# ATMEGA328.net
KiCad netlist of a schematic drawn in EAGLE
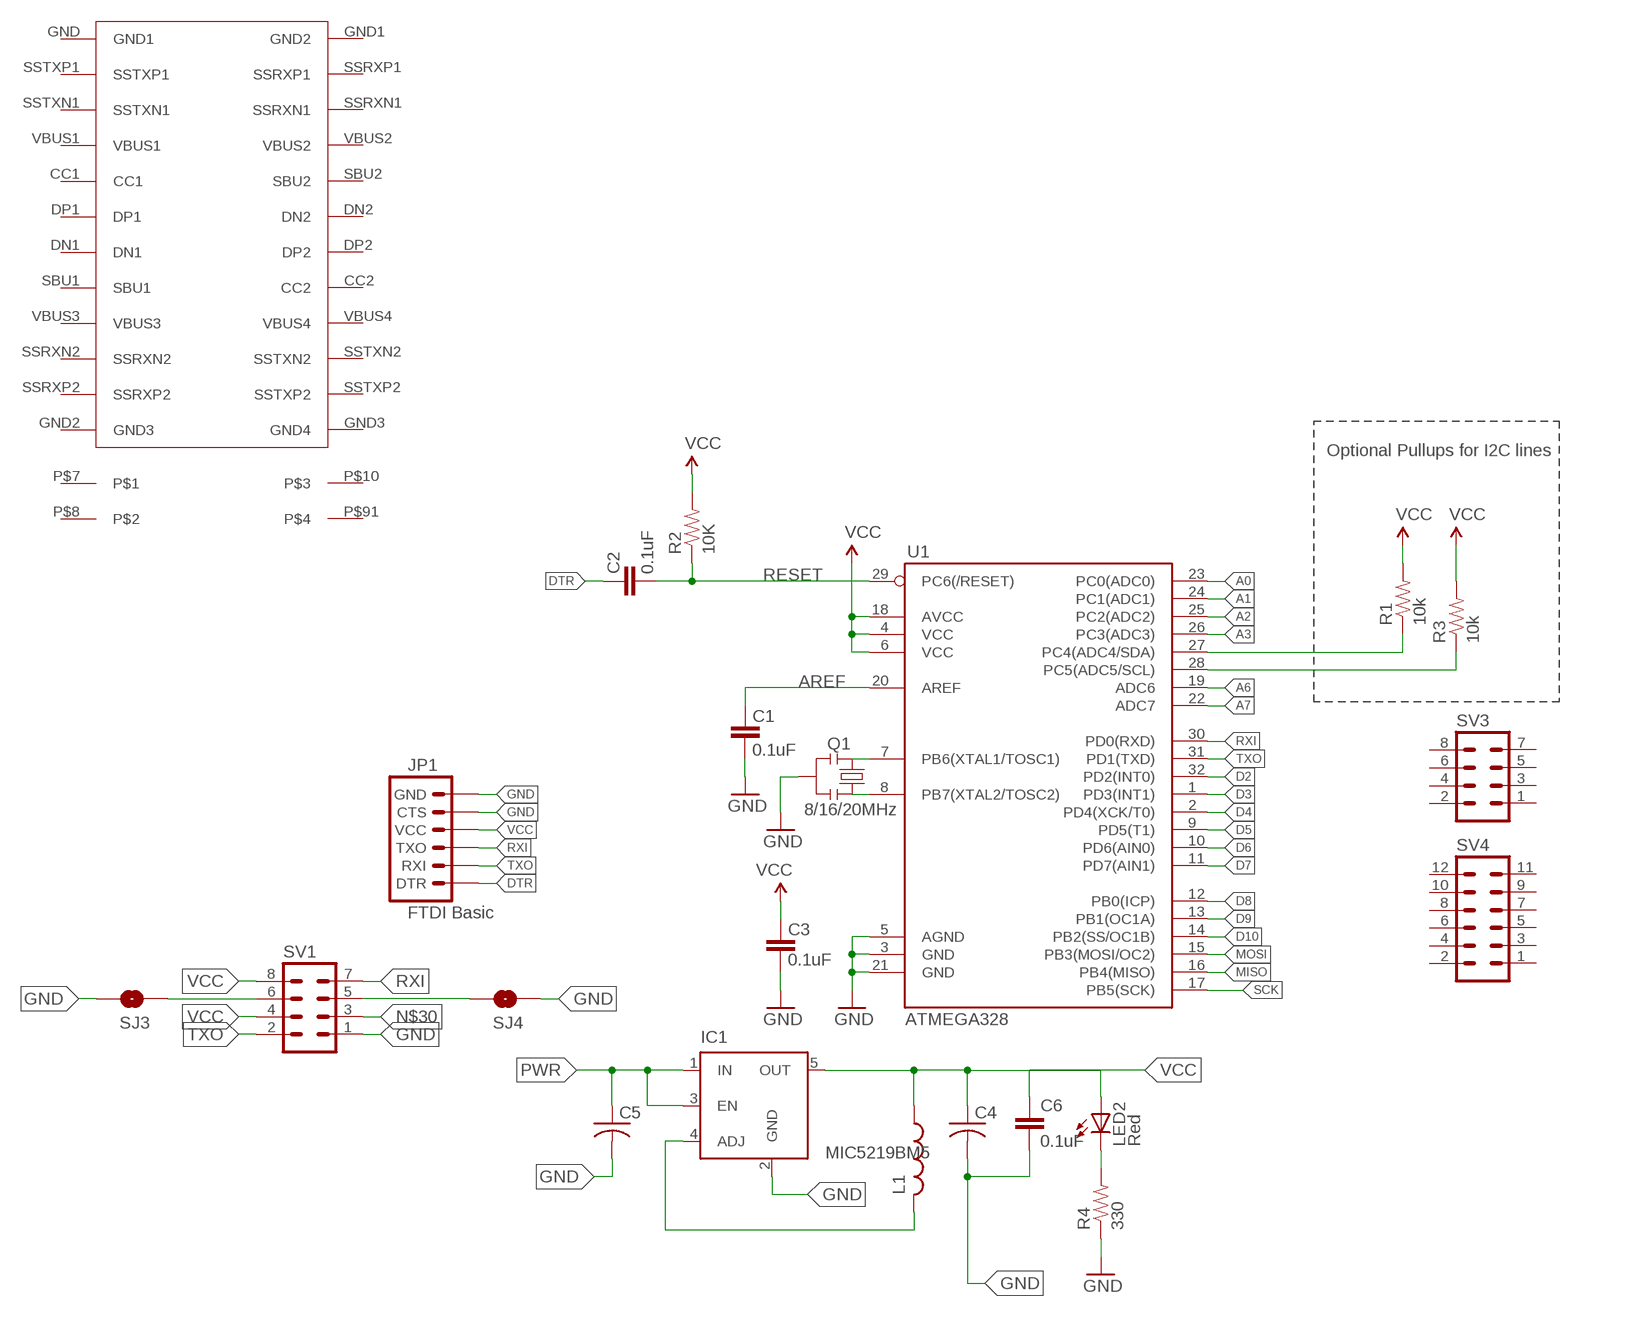
[diagram p0: schematic, sheet 1]

(export (version "E")
  (design (tool "Eeschema 10.0.6"))
  (components
    (comp (ref "C1")
      (value "0.1uF")
      (footprint "eagle-import:0603-CAP")
      (libsource (lib "eagle-import") (part "CAP0603-CAP"))
    )
    (comp (ref "C2")
      (value "0.1uF")
      (footprint "eagle-import:0603-CAP")
      (libsource (lib "eagle-import") (part "CAP0603-CAP"))
    )
    (comp (ref "C3")
      (value "0.1uF")
      (footprint "eagle-import:0603-CAP")
      (libsource (lib "eagle-import") (part "CAP0603-CAP"))
    )
    (comp (ref "C4")
      (value "C-USC0805K")
      (footprint "eagle-import:C0805K")
      (libsource (lib "eagle-import") (part "C-USC0805K"))
    )
    (comp (ref "C5")
      (value "C-USC0805K")
      (footprint "eagle-import:C0805K")
      (libsource (lib "eagle-import") (part "C-USC0805K"))
    )
    (comp (ref "C6")
      (value "0.1uF")
      (footprint "eagle-import:0603-CAP")
      (libsource (lib "eagle-import") (part "CAP0603-CAP"))
    )
    (comp (ref "IC1")
      (value "MIC5219BM5")
      (footprint "eagle-import:SOT23-5")
      (fields (field (name "MF") "ALTERA CORPORATION") (field (name "MPN") "MIC5219BM5 TR"))
      (libsource (lib "eagle-import") (part "MIC5219BM5"))
    )
    (comp (ref "JP1")
      (value "FTDI Basic")
      (footprint "eagle-import:1X06")
      (libsource (lib "eagle-import") (part "ARDUINO_SERIAL_PROGRAMPTH"))
    )
    (comp (ref "L1")
      (value "L-USL2012C")
      (footprint "eagle-import:L2012C")
      (libsource (lib "eagle-import") (part "L-USL2012C"))
    )
    (comp (ref "LED2")
      (value "Red")
      (footprint "eagle-import:0603-LED-ALT1")
      (libsource (lib "eagle-import") (part "LED"))
    )
    (comp (ref "Q1")
      (value "8/16/20MHz")
      (footprint "eagle-import:RESONATOR-SMD-1_1")
      (libsource (lib "eagle-import") (part "RESONATOR1{colon}1"))
    )
    (comp (ref "R1")
      (value "10k")
      (footprint "eagle-import:0603-RES")
      (libsource (lib "eagle-import") (part "RESISTOR0603-RES"))
    )
    (comp (ref "R2")
      (value "10K")
      (footprint "eagle-import:0603-RES")
      (libsource (lib "eagle-import") (part "RESISTOR0603-RES"))
    )
    (comp (ref "R3")
      (value "10k")
      (footprint "eagle-import:0603-RES")
      (libsource (lib "eagle-import") (part "RESISTOR0603-RES"))
    )
    (comp (ref "R4")
      (value "330")
      (footprint "eagle-import:0603-RES")
      (libsource (lib "eagle-import") (part "RESISTOR0603-RES"))
    )
    (comp (ref "SJ3")
      (value "SOLDERJUMPERNC")
      (footprint "eagle-import:SJ_2S")
      (libsource (lib "eagle-import") (part "SOLDERJUMPERNC"))
    )
    (comp (ref "SJ4")
      (value "SOLDERJUMPERNC")
      (footprint "eagle-import:SJ_2S")
      (libsource (lib "eagle-import") (part "SOLDERJUMPERNC"))
    )
    (comp (ref "SV1")
      (value "MA04-2")
      (footprint "eagle-import:MA04-2")
      (libsource (lib "eagle-import") (part "MA04-2"))
    )
    (comp (ref "SV3")
      (value "MA04-2")
      (footprint "eagle-import:MA04-2")
      (libsource (lib "eagle-import") (part "MA04-2"))
    )
    (comp (ref "SV4")
      (value "MA06-2")
      (footprint "eagle-import:MA06-2")
      (libsource (lib "eagle-import") (part "MA06-2"))
    )
    (comp (ref "U$1")
      (value "USB-C")
      (footprint "eagle-import:USB-C")
      (libsource (lib "eagle-import") (part "USB-C"))
    )
    (comp (ref "U1")
      (value "ATMEGA328")
      (footprint "eagle-import:TQFP32-08")
      (libsource (lib "eagle-import") (part "ATMEGA168"))
    )
  )
  (nets
    (net (code "1") (name "/AREF") (class "Default")
      (node (ref "C1") (pin "2") (pinfunction "2_2") (pintype "passive"))
      (node (ref "U1") (pin "20") (pinfunction "AREF_20") (pintype "bidirectional"))
    )
    (net (code "2") (name "/RESET") (class "Default")
      (node (ref "C2") (pin "1") (pinfunction "1_1") (pintype "passive"))
      (node (ref "R2") (pin "1") (pinfunction "1_1") (pintype "passive"))
      (node (ref "U1") (pin "29") (pinfunction "PC6(/RESET)_29") (pintype "bidirectional"))
    )
    (net (code "3") (name "A0") (class "Default")
      (node (ref "U1") (pin "23") (pinfunction "PC0(ADC0)_23") (pintype "bidirectional"))
    )
    (net (code "4") (name "A1") (class "Default")
      (node (ref "U1") (pin "24") (pinfunction "PC1(ADC1)_24") (pintype "bidirectional"))
    )
    (net (code "5") (name "A2") (class "Default")
      (node (ref "U1") (pin "25") (pinfunction "PC2(ADC2)_25") (pintype "bidirectional"))
    )
    (net (code "6") (name "A3") (class "Default")
      (node (ref "U1") (pin "26") (pinfunction "PC3(ADC3)_26") (pintype "bidirectional"))
    )
    (net (code "7") (name "A6") (class "Default")
      (node (ref "U1") (pin "19") (pinfunction "ADC6_19") (pintype "bidirectional"))
    )
    (net (code "8") (name "A7") (class "Default")
      (node (ref "U1") (pin "22") (pinfunction "ADC7_22") (pintype "bidirectional"))
    )
    (net (code "9") (name "D2") (class "Default")
      (node (ref "U1") (pin "32") (pinfunction "PD2(INT0)_32") (pintype "bidirectional"))
    )
    (net (code "10") (name "D3") (class "Default")
      (node (ref "U1") (pin "1") (pinfunction "PD3(INT1)_1") (pintype "bidirectional"))
    )
    (net (code "11") (name "D4") (class "Default")
      (node (ref "U1") (pin "2") (pinfunction "PD4(XCK/T0)_2") (pintype "bidirectional"))
    )
    (net (code "12") (name "D5") (class "Default")
      (node (ref "U1") (pin "9") (pinfunction "PD5(T1)_9") (pintype "bidirectional"))
    )
    (net (code "13") (name "D6") (class "Default")
      (node (ref "U1") (pin "10") (pinfunction "PD6(AIN0)_10") (pintype "bidirectional"))
    )
    (net (code "14") (name "D7") (class "Default")
      (node (ref "U1") (pin "11") (pinfunction "PD7(AIN1)_11") (pintype "bidirectional"))
    )
    (net (code "15") (name "D8") (class "Default")
      (node (ref "U1") (pin "12") (pinfunction "PB0(ICP)_12") (pintype "bidirectional"))
    )
    (net (code "16") (name "D9") (class "Default")
      (node (ref "U1") (pin "13") (pinfunction "PB1(OC1A)_13") (pintype "bidirectional"))
    )
    (net (code "17") (name "D10") (class "Default")
      (node (ref "U1") (pin "14") (pinfunction "PB2(SS/OC1B)_14") (pintype "bidirectional"))
    )
    (net (code "18") (name "DTR") (class "Default")
      (node (ref "C2") (pin "2") (pinfunction "2_2") (pintype "passive"))
      (node (ref "JP1") (pin "1") (pinfunction "DTR_1") (pintype "passive"))
    )
    (net (code "19") (name "GND") (class "Default")
      (node (ref "C1") (pin "1") (pinfunction "1_1") (pintype "passive"))
      (node (ref "C3") (pin "1") (pinfunction "1_1") (pintype "passive"))
      (node (ref "C4") (pin "2") (pinfunction "2_2") (pintype "passive"))
      (node (ref "C5") (pin "2") (pinfunction "2_2") (pintype "passive"))
      (node (ref "C6") (pin "2") (pinfunction "2_2") (pintype "passive"))
      (node (ref "IC1") (pin "2") (pinfunction "GND_2") (pintype "power_in"))
      (node (ref "JP1") (pin "5") (pinfunction "CTS_5") (pintype "passive"))
      (node (ref "JP1") (pin "6") (pinfunction "GND_6") (pintype "passive"))
      (node (ref "Q1") (pin "2") (pinfunction "2_2") (pintype "passive"))
      (node (ref "R4") (pin "1") (pinfunction "1_1") (pintype "passive"))
      (node (ref "SJ3") (pin "2") (pinfunction "2_2") (pintype "passive"))
      (node (ref "SJ4") (pin "1") (pinfunction "1_1") (pintype "passive"))
      (node (ref "SV1") (pin "1") (pinfunction "1_1") (pintype "passive"))
      (node (ref "U1") (pin "21") (pinfunction "GND_21") (pintype "bidirectional"))
      (node (ref "U1") (pin "3") (pinfunction "GND_3") (pintype "bidirectional"))
      (node (ref "U1") (pin "5") (pinfunction "AGND_5") (pintype "bidirectional"))
    )
    (net (code "20") (name "MISO") (class "Default")
      (node (ref "U1") (pin "16") (pinfunction "PB4(MISO)_16") (pintype "bidirectional"))
    )
    (net (code "21") (name "MOSI") (class "Default")
      (node (ref "U1") (pin "15") (pinfunction "PB3(MOSI/OC2)_15") (pintype "bidirectional"))
    )
    (net (code "22") (name "N$30") (class "Default")
      (node (ref "SV1") (pin "3") (pinfunction "3_3") (pintype "passive"))
    )
    (net (code "23") (name "Net-(IC1-ADJ)") (class "Default")
      (node (ref "IC1") (pin "4") (pinfunction "ADJ_4") (pintype "passive"))
      (node (ref "L1") (pin "2") (pinfunction "2_2") (pintype "passive"))
    )
    (net (code "24") (name "Net-(LED2-PadC)") (class "Default")
      (node (ref "LED2") (pin "C") (pinfunction "C_C") (pintype "passive"))
      (node (ref "R4") (pin "2") (pinfunction "2_2") (pintype "passive"))
    )
    (net (code "25") (name "Net-(SJ3-Pad1)") (class "Default")
      (node (ref "SJ3") (pin "1") (pinfunction "1_1") (pintype "passive"))
      (node (ref "SV1") (pin "6") (pinfunction "6_6") (pintype "passive"))
    )
    (net (code "26") (name "Net-(SJ4-Pad2)") (class "Default")
      (node (ref "SJ4") (pin "2") (pinfunction "2_2") (pintype "passive"))
      (node (ref "SV1") (pin "5") (pinfunction "5_5") (pintype "passive"))
    )
    (net (code "27") (name "Net-(U1-PB6(XTAL1{slash}TOSC1))") (class "Default")
      (node (ref "Q1") (pin "1") (pinfunction "1_1") (pintype "passive"))
      (node (ref "U1") (pin "7") (pinfunction "PB6(XTAL1/TOSC1)_7") (pintype "bidirectional"))
    )
    (net (code "28") (name "Net-(U1-PB7(XTAL2{slash}TOSC2))") (class "Default")
      (node (ref "Q1") (pin "3") (pinfunction "3_3") (pintype "passive"))
      (node (ref "U1") (pin "8") (pinfunction "PB7(XTAL2/TOSC2)_8") (pintype "bidirectional"))
    )
    (net (code "29") (name "Net-(U1-PC4(ADC4{slash}SDA))") (class "Default")
      (node (ref "R1") (pin "1") (pinfunction "1_1") (pintype "passive"))
      (node (ref "U1") (pin "27") (pinfunction "PC4(ADC4/SDA)_27") (pintype "bidirectional"))
    )
    (net (code "30") (name "Net-(U1-PC5(ADC5{slash}SCL))") (class "Default")
      (node (ref "R3") (pin "1") (pinfunction "1_1") (pintype "passive"))
      (node (ref "U1") (pin "28") (pinfunction "PC5(ADC5/SCL)_28") (pintype "bidirectional"))
    )
    (net (code "31") (name "PWR") (class "Default")
      (node (ref "C5") (pin "1") (pinfunction "1_1") (pintype "passive"))
      (node (ref "IC1") (pin "1") (pinfunction "IN_1") (pintype "input"))
      (node (ref "IC1") (pin "3") (pinfunction "EN_3") (pintype "input"))
    )
    (net (code "32") (name "RXI") (class "Default")
      (node (ref "JP1") (pin "3") (pinfunction "TXO_3") (pintype "passive"))
      (node (ref "SV1") (pin "7") (pinfunction "7_7") (pintype "passive"))
      (node (ref "U1") (pin "30") (pinfunction "PD0(RXD)_30") (pintype "bidirectional"))
    )
    (net (code "33") (name "SCK") (class "Default")
      (node (ref "U1") (pin "17") (pinfunction "PB5(SCK)_17") (pintype "bidirectional"))
    )
    (net (code "34") (name "TXO") (class "Default")
      (node (ref "JP1") (pin "2") (pinfunction "RXI_2") (pintype "passive"))
      (node (ref "SV1") (pin "2") (pinfunction "2_2") (pintype "passive"))
      (node (ref "U1") (pin "31") (pinfunction "PD1(TXD)_31") (pintype "bidirectional"))
    )
    (net (code "35") (name "VCC") (class "Default")
      (node (ref "C3") (pin "2") (pinfunction "2_2") (pintype "passive"))
      (node (ref "C4") (pin "1") (pinfunction "1_1") (pintype "passive"))
      (node (ref "C6") (pin "1") (pinfunction "1_1") (pintype "passive"))
      (node (ref "IC1") (pin "5") (pinfunction "OUT_5") (pintype "output"))
      (node (ref "JP1") (pin "4") (pinfunction "VCC_4") (pintype "passive"))
      (node (ref "L1") (pin "1") (pinfunction "1_1") (pintype "passive"))
      (node (ref "LED2") (pin "A") (pinfunction "A_A") (pintype "passive"))
      (node (ref "R1") (pin "2") (pinfunction "2_2") (pintype "passive"))
      (node (ref "R2") (pin "2") (pinfunction "2_2") (pintype "passive"))
      (node (ref "R3") (pin "2") (pinfunction "2_2") (pintype "passive"))
      (node (ref "SV1") (pin "4") (pinfunction "4_4") (pintype "passive"))
      (node (ref "SV1") (pin "8") (pinfunction "8_8") (pintype "passive"))
      (node (ref "U1") (pin "18") (pinfunction "AVCC_18") (pintype "bidirectional"))
      (node (ref "U1") (pin "4") (pinfunction "VCC_4") (pintype "bidirectional"))
      (node (ref "U1") (pin "6") (pinfunction "VCC_6") (pintype "bidirectional"))
    )
    (net (code "36") (name "unconnected-(SV3-Pad1)") (class "Default")
      (node (ref "SV3") (pin "1") (pinfunction "1_1") (pintype "passive"))
    )
    (net (code "37") (name "unconnected-(SV3-Pad2)") (class "Default")
      (node (ref "SV3") (pin "2") (pinfunction "2_2") (pintype "passive"))
    )
    (net (code "38") (name "unconnected-(SV3-Pad3)") (class "Default")
      (node (ref "SV3") (pin "3") (pinfunction "3_3") (pintype "passive"))
    )
    (net (code "39") (name "unconnected-(SV3-Pad4)") (class "Default")
      (node (ref "SV3") (pin "4") (pinfunction "4_4") (pintype "passive"))
    )
    (net (code "40") (name "unconnected-(SV3-Pad5)") (class "Default")
      (node (ref "SV3") (pin "5") (pinfunction "5_5") (pintype "passive"))
    )
    (net (code "41") (name "unconnected-(SV3-Pad6)") (class "Default")
      (node (ref "SV3") (pin "6") (pinfunction "6_6") (pintype "passive"))
    )
    (net (code "42") (name "unconnected-(SV3-Pad7)") (class "Default")
      (node (ref "SV3") (pin "7") (pinfunction "7_7") (pintype "passive"))
    )
    (net (code "43") (name "unconnected-(SV3-Pad8)") (class "Default")
      (node (ref "SV3") (pin "8") (pinfunction "8_8") (pintype "passive"))
    )
    (net (code "44") (name "unconnected-(SV4-Pad1)") (class "Default")
      (node (ref "SV4") (pin "1") (pinfunction "1_1") (pintype "passive"))
    )
    (net (code "45") (name "unconnected-(SV4-Pad2)") (class "Default")
      (node (ref "SV4") (pin "2") (pinfunction "2_2") (pintype "passive"))
    )
    (net (code "46") (name "unconnected-(SV4-Pad3)") (class "Default")
      (node (ref "SV4") (pin "3") (pinfunction "3_3") (pintype "passive"))
    )
    (net (code "47") (name "unconnected-(SV4-Pad4)") (class "Default")
      (node (ref "SV4") (pin "4") (pinfunction "4_4") (pintype "passive"))
    )
    (net (code "48") (name "unconnected-(SV4-Pad5)") (class "Default")
      (node (ref "SV4") (pin "5") (pinfunction "5_5") (pintype "passive"))
    )
    (net (code "49") (name "unconnected-(SV4-Pad6)") (class "Default")
      (node (ref "SV4") (pin "6") (pinfunction "6_6") (pintype "passive"))
    )
    (net (code "50") (name "unconnected-(SV4-Pad7)") (class "Default")
      (node (ref "SV4") (pin "7") (pinfunction "7_7") (pintype "passive"))
    )
    (net (code "51") (name "unconnected-(SV4-Pad8)") (class "Default")
      (node (ref "SV4") (pin "8") (pinfunction "8_8") (pintype "passive"))
    )
    (net (code "52") (name "unconnected-(SV4-Pad9)") (class "Default")
      (node (ref "SV4") (pin "9") (pinfunction "9_9") (pintype "passive"))
    )
    (net (code "53") (name "unconnected-(SV4-Pad10)") (class "Default")
      (node (ref "SV4") (pin "10") (pinfunction "10_10") (pintype "passive"))
    )
    (net (code "54") (name "unconnected-(SV4-Pad11)") (class "Default")
      (node (ref "SV4") (pin "11") (pinfunction "11_11") (pintype "passive"))
    )
    (net (code "55") (name "unconnected-(SV4-Pad12)") (class "Default")
      (node (ref "SV4") (pin "12") (pinfunction "12_12") (pintype "passive"))
    )
    (net (code "56") (name "unconnected-(U$1-GND1-PadGND)") (class "Default")
      (node (ref "U$1") (pin "GND") (pinfunction "GND1_GND") (pintype "bidirectional"))
    )
    (net (code "57") (name "unconnected-(U$1-GND2-PadGND1)") (class "Default")
      (node (ref "U$1") (pin "GND1") (pinfunction "GND2_GND1") (pintype "bidirectional"))
    )
    (net (code "58") (name "unconnected-(U$1-GND3-PadGND2)") (class "Default")
      (node (ref "U$1") (pin "GND2") (pinfunction "GND3_GND2") (pintype "bidirectional"))
    )
    (net (code "59") (name "unconnected-(U$1-GND4-PadGND3)") (class "Default")
      (node (ref "U$1") (pin "GND3") (pinfunction "GND4_GND3") (pintype "bidirectional"))
    )
    (net (code "60") (name "unconnected-(U$1-P$1-PadP$7)") (class "Default")
      (node (ref "U$1") (pin "P$7") (pinfunction "P$1_P$7") (pintype "bidirectional"))
    )
    (net (code "61") (name "unconnected-(U$1-P$2-PadP$8)") (class "Default")
      (node (ref "U$1") (pin "P$8") (pinfunction "P$2_P$8") (pintype "bidirectional"))
    )
    (net (code "62") (name "unconnected-(U$1-P$3-PadP$10)") (class "Default")
      (node (ref "U$1") (pin "P$10") (pinfunction "P$3_P$10") (pintype "bidirectional"))
    )
    (net (code "63") (name "unconnected-(U$1-P$4-PadP$91)") (class "Default")
      (node (ref "U$1") (pin "P$91") (pinfunction "P$4_P$91") (pintype "bidirectional"))
    )
    (net (code "64") (name "unconnected-(U$1-PadCC1)") (class "Default")
      (node (ref "U$1") (pin "CC1") (pinfunction "CC1_CC1") (pintype "bidirectional"))
    )
    (net (code "65") (name "unconnected-(U$1-PadCC2)") (class "Default")
      (node (ref "U$1") (pin "CC2") (pinfunction "CC2_CC2") (pintype "bidirectional"))
    )
    (net (code "66") (name "unconnected-(U$1-PadDN1)") (class "Default")
      (node (ref "U$1") (pin "DN1") (pinfunction "DN1_DN1") (pintype "bidirectional"))
    )
    (net (code "67") (name "unconnected-(U$1-PadDN2)") (class "Default")
      (node (ref "U$1") (pin "DN2") (pinfunction "DN2_DN2") (pintype "bidirectional"))
    )
    (net (code "68") (name "unconnected-(U$1-PadDP1)") (class "Default")
      (node (ref "U$1") (pin "DP1") (pinfunction "DP1_DP1") (pintype "bidirectional"))
    )
    (net (code "69") (name "unconnected-(U$1-PadDP2)") (class "Default")
      (node (ref "U$1") (pin "DP2") (pinfunction "DP2_DP2") (pintype "bidirectional"))
    )
    (net (code "70") (name "unconnected-(U$1-PadSBU1)") (class "Default")
      (node (ref "U$1") (pin "SBU1") (pinfunction "SBU1_SBU1") (pintype "bidirectional"))
    )
    (net (code "71") (name "unconnected-(U$1-PadSBU2)") (class "Default")
      (node (ref "U$1") (pin "SBU2") (pinfunction "SBU2_SBU2") (pintype "bidirectional"))
    )
    (net (code "72") (name "unconnected-(U$1-PadSSRXN1)") (class "Default")
      (node (ref "U$1") (pin "SSRXN1") (pinfunction "SSRXN1_SSRXN1") (pintype "bidirectional"))
    )
    (net (code "73") (name "unconnected-(U$1-PadSSRXN2)") (class "Default")
      (node (ref "U$1") (pin "SSRXN2") (pinfunction "SSRXN2_SSRXN2") (pintype "bidirectional"))
    )
    (net (code "74") (name "unconnected-(U$1-PadSSRXP1)") (class "Default")
      (node (ref "U$1") (pin "SSRXP1") (pinfunction "SSRXP1_SSRXP1") (pintype "bidirectional"))
    )
    (net (code "75") (name "unconnected-(U$1-PadSSRXP2)") (class "Default")
      (node (ref "U$1") (pin "SSRXP2") (pinfunction "SSRXP2_SSRXP2") (pintype "bidirectional"))
    )
    (net (code "76") (name "unconnected-(U$1-PadSSTXN1)") (class "Default")
      (node (ref "U$1") (pin "SSTXN1") (pinfunction "SSTXN1_SSTXN1") (pintype "bidirectional"))
    )
    (net (code "77") (name "unconnected-(U$1-PadSSTXN2)") (class "Default")
      (node (ref "U$1") (pin "SSTXN2") (pinfunction "SSTXN2_SSTXN2") (pintype "bidirectional"))
    )
    (net (code "78") (name "unconnected-(U$1-PadSSTXP1)") (class "Default")
      (node (ref "U$1") (pin "SSTXP1") (pinfunction "SSTXP1_SSTXP1") (pintype "bidirectional"))
    )
    (net (code "79") (name "unconnected-(U$1-PadSSTXP2)") (class "Default")
      (node (ref "U$1") (pin "SSTXP2") (pinfunction "SSTXP2_SSTXP2") (pintype "bidirectional"))
    )
    (net (code "80") (name "unconnected-(U$1-PadVBUS1)") (class "Default")
      (node (ref "U$1") (pin "VBUS1") (pinfunction "VBUS1_VBUS1") (pintype "bidirectional"))
    )
    (net (code "81") (name "unconnected-(U$1-PadVBUS2)") (class "Default")
      (node (ref "U$1") (pin "VBUS2") (pinfunction "VBUS2_VBUS2") (pintype "bidirectional"))
    )
    (net (code "82") (name "unconnected-(U$1-PadVBUS3)") (class "Default")
      (node (ref "U$1") (pin "VBUS3") (pinfunction "VBUS3_VBUS3") (pintype "bidirectional"))
    )
    (net (code "83") (name "unconnected-(U$1-PadVBUS4)") (class "Default")
      (node (ref "U$1") (pin "VBUS4") (pinfunction "VBUS4_VBUS4") (pintype "bidirectional"))
    )
  )
)
